# Power_Neg.net
KiCad netlist of a schematic drawn in Altium Designer
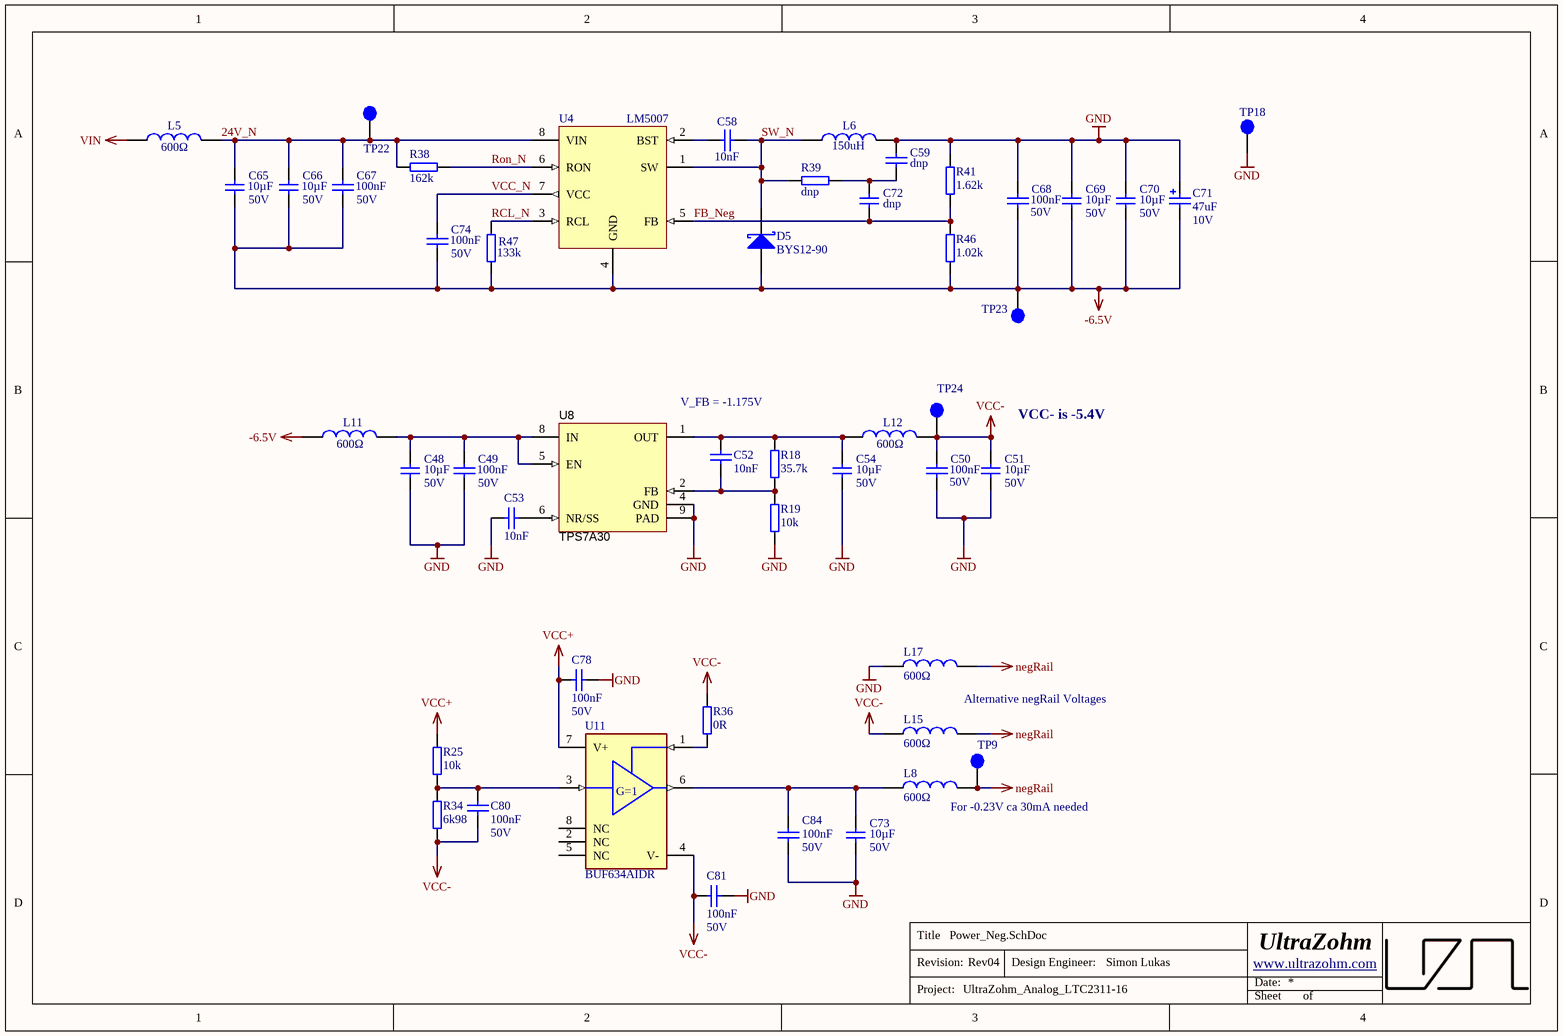
[diagram p0: Power_Neg.SchDoc]

(export (version "E")
  (design (tool "Eeschema 10.0.6"))
  (components
    (comp (ref "C48")
      (value "10µF")
      (footprint "C_1206")
      (description "Capacitor 1206")
      (fields
        (field (name "TOLERANCE") "10%")
        (field (name "MF") "Samsung")
        (field (name "VOLTAGE") "50V")
        (field (name "CREATED") "2020_09_17_Liegmann")
      )
      (libsource (lib "UltraZohm_ADC") (part "C_1206"))
    )
    (comp (ref "C49")
      (value "100nF")
      (footprint "CAPC1608X07N")
      (fields
        (field (name "MF") "Yageo")
        (field (name "MPN") "CC0603KRX7R9BB104")
        (field (name "VOLTAGE") "50V")
        (field (name "TOLERANCE") "10%")
      )
      (libsource (lib "UltraZohm_ADC") (part "Cap_0603"))
    )
    (comp (ref "C50")
      (value "100nF")
      (footprint "CAPC1608X07N")
      (fields
        (field (name "MF") "Yageo")
        (field (name "MPN") "CC0603KRX7R9BB104")
        (field (name "VOLTAGE") "50V")
        (field (name "TOLERANCE") "10%")
      )
      (libsource (lib "UltraZohm_ADC") (part "Cap_0603"))
    )
    (comp (ref "C51")
      (value "10µF")
      (footprint "C_1206")
      (description "Capacitor 1206")
      (fields
        (field (name "TOLERANCE") "10%")
        (field (name "MF") "Samsung")
        (field (name "VOLTAGE") "50V")
        (field (name "CREATED") "2020_09_17_Liegmann")
      )
      (libsource (lib "UltraZohm_ADC") (part "C_1206"))
    )
    (comp (ref "C52")
      (value "10nF")
      (footprint "CAPC1608X07N")
      (fields
        (field (name "MF") "Würth Elektronik")
        (field (name "MPN") "885012206065")
        (field (name "VOLTAGE") "25V")
      )
      (libsource (lib "UltraZohm_ADC") (part "Cap_0603"))
    )
    (comp (ref "C53")
      (value "10nF")
      (footprint "CAPC1608X07N")
      (fields
        (field (name "MF") "Würth Elektronik")
        (field (name "MPN") "885012206065")
        (field (name "VOLTAGE") "25V")
      )
      (libsource (lib "UltraZohm_ADC") (part "Cap_0603"))
    )
    (comp (ref "C54")
      (value "10µF")
      (footprint "C_1206")
      (description "Capacitor 1206")
      (fields
        (field (name "TOLERANCE") "10%")
        (field (name "MF") "Samsung")
        (field (name "VOLTAGE") "50V")
        (field (name "CREATED") "2020_09_17_Liegmann")
      )
      (libsource (lib "UltraZohm_ADC") (part "C_1206"))
    )
    (comp (ref "C58")
      (value "10nF")
      (footprint "CAPC1608X07N")
      (fields
        (field (name "MF") "Würth Elektronik")
        (field (name "MPN") "885012206065")
        (field (name "VOLTAGE") "25V")
      )
      (libsource (lib "UltraZohm_ADC") (part "Cap_0603"))
    )
    (comp (ref "C59")
      (value "dnp")
      (footprint "CAPC1608X07N")
      (fields
        (field (name "MF") "KEMET")
        (field (name "MPN") "C0603C752J3GACTU")
        (field (name "VOLTAGE") "25V")
      )
      (libsource (lib "UltraZohm_ADC") (part "Cap_0603"))
    )
    (comp (ref "C65")
      (value "10µF")
      (footprint "C_1206")
      (description "Capacitor 1206")
      (fields (field (name "TOLERANCE") "20%") (field (name "MF") "Samsung") (field (name "VOLTAGE") "50V"))
      (libsource (lib "UltraZohm_ADC") (part "C_1206"))
    )
    (comp (ref "C66")
      (value "10µF")
      (footprint "C_1206")
      (description "Capacitor 1206")
      (fields (field (name "TOLERANCE") "20%") (field (name "MF") "Samsung") (field (name "VOLTAGE") "50V"))
      (libsource (lib "UltraZohm_ADC") (part "C_1206"))
    )
    (comp (ref "C67")
      (value "100nF")
      (footprint "CAPC1608X07N")
      (fields
        (field (name "MF") "Yageo")
        (field (name "MPN") "CC0603KRX7R9BB104")
        (field (name "VOLTAGE") "50V")
        (field (name "TOLERANCE") "10%")
      )
      (libsource (lib "UltraZohm_ADC") (part "Cap_0603"))
    )
    (comp (ref "C68")
      (value "100nF")
      (footprint "CAPC1608X07N")
      (fields
        (field (name "MF") "Yageo")
        (field (name "MPN") "CC0603KRX7R9BB104")
        (field (name "VOLTAGE") "50V")
        (field (name "TOLERANCE") "10%")
      )
      (libsource (lib "UltraZohm_ADC") (part "Cap_0603"))
    )
    (comp (ref "C69")
      (value "10µF")
      (footprint "C_1206")
      (description "Capacitor 1206")
      (fields
        (field (name "TOLERANCE") "10%")
        (field (name "MF") "Samsung")
        (field (name "VOLTAGE") "50V")
        (field (name "CREATED") "2020_09_17_Liegmann")
      )
      (libsource (lib "UltraZohm_ADC") (part "C_1206"))
    )
    (comp (ref "C70")
      (value "10µF")
      (footprint "C_1206")
      (description "Capacitor 1206")
      (fields
        (field (name "TOLERANCE") "10%")
        (field (name "MF") "Samsung")
        (field (name "VOLTAGE") "50V")
        (field (name "CREATED") "2020_09_17_Liegmann")
      )
      (libsource (lib "UltraZohm_ADC") (part "C_1206"))
    )
    (comp (ref "C71")
      (value "47uF")
      (footprint "WCAP-ASLI_5x5.5")
      (description "WCAP-ASLI Aluminum Electrolytic Capacitor, V-Chip, SMT, D5xH5.5mm, 47uF, 10V")
      (fields
        (field (name "MPN") "865080242004")
        (field (name "MF") "Wurth Elektronik")
        (field (name "VOLTAGE") "10V")
      )
      (libsource (lib "UltraZohm_ADC") (part "865080142007"))
    )
    (comp (ref "C72")
      (value "dnp")
      (footprint "C_1206")
      (description "Capacitor 1206")
      (fields (field (name "TOLERANCE") "5%") (field (name "MF") "Murata Electronics"))
      (libsource (lib "UltraZohm_ADC") (part "C_1206"))
    )
    (comp (ref "C73")
      (value "10µF")
      (footprint "C_1206")
      (description "Capacitor 1206")
      (fields
        (field (name "TOLERANCE") "10%")
        (field (name "MF") "Samsung")
        (field (name "VOLTAGE") "50V")
        (field (name "CREATED") "2020_09_17_Liegmann")
      )
      (libsource (lib "UltraZohm_ADC") (part "C_1206"))
    )
    (comp (ref "C74")
      (value "100nF")
      (footprint "CAPC1608X07N")
      (fields
        (field (name "MF") "Yageo")
        (field (name "MPN") "CC0603KRX7R9BB104")
        (field (name "VOLTAGE") "50V")
        (field (name "TOLERANCE") "10%")
      )
      (libsource (lib "UltraZohm_ADC") (part "Cap_0603"))
    )
    (comp (ref "C78")
      (value "100nF")
      (footprint "CAPC1608X07N")
      (fields
        (field (name "MF") "Yageo")
        (field (name "MPN") "CC0603KRX7R9BB104")
        (field (name "VOLTAGE") "50V")
      )
      (libsource (lib "UltraZohm_ADC") (part "Cap_0603"))
    )
    (comp (ref "C80")
      (value "100nF")
      (footprint "CAPC1608X07N")
      (fields
        (field (name "MF") "Yageo")
        (field (name "MPN") "CC0603KRX7R9BB104")
        (field (name "VOLTAGE") "50V")
      )
      (libsource (lib "UltraZohm_ADC") (part "Cap_0603"))
    )
    (comp (ref "C81")
      (value "100nF")
      (footprint "CAPC1608X07N")
      (fields
        (field (name "MF") "Yageo")
        (field (name "MPN") "CC0603KRX7R9BB104")
        (field (name "VOLTAGE") "50V")
      )
      (libsource (lib "UltraZohm_ADC") (part "Cap_0603"))
    )
    (comp (ref "C84")
      (value "100nF")
      (footprint "CAPC1608X07N")
      (fields
        (field (name "MF") "Yageo")
        (field (name "MPN") "CC0603KRX7R9BB104")
        (field (name "VOLTAGE") "50V")
      )
      (libsource (lib "UltraZohm_ADC") (part "Cap_0603"))
    )
    (comp (ref "D5")
      (value "BYS12-90")
      (footprint "DIOM4227X23N")
      (description "Schottky Diode")
      (fields (field (name "MF") "Vishay") (field (name "MPN") "BYS12-90-E3/TR3"))
      (libsource (lib "UltraZohm_ADC") (part "BYS12-90"))
    )
    (comp (ref "L5")
      (value "600Ω")
      (footprint "WE-CBF_0805_High Current")
      (description "WE-CBF SMD EMI Suppression Ferrite Bead, 0805, 600Ω")
      (fields (field (name "MF") "Würth Elektronik") (field (name "MPN") "742792040"))
      (libsource (lib "UltraZohm_ADC") (part "WE-CBF, 742792040"))
    )
    (comp (ref "L6")
      (value "150uH")
      (footprint "SMT_inductor_1050_Performance")
      (description "SMT power Inductor, 150uH, 320m DRC")
      (fields (field (name "MF") "EPCOS / TDK") (field (name "MPN") "B82464G4154M"))
      (libsource (lib "UltraZohm_ADC") (part "B82464G4154M"))
    )
    (comp (ref "L8")
      (value "600Ω")
      (footprint "WE-CBF_0805_High Current")
      (description "WE-CBF SMD EMI Suppression Ferrite Bead, 0805, 600Ω")
      (fields (field (name "MF") "Wurth Elektronik") (field (name "MPN") "742792040"))
      (libsource (lib "UltraZohm_ADC") (part "WE-CBF, 742792040"))
    )
    (comp (ref "L11")
      (value "600Ω")
      (footprint "WE-CBF_0805_High Current")
      (description "WE-CBF SMD EMI Suppression Ferrite Bead, 0805, 600Ω")
      (fields (field (name "MF") "Würth Elektronik") (field (name "MPN") "742792040"))
      (libsource (lib "UltraZohm_ADC") (part "WE-CBF, 742792040"))
    )
    (comp (ref "L12")
      (value "600Ω")
      (footprint "WE-CBF_0805_High Current")
      (description "WE-CBF SMD EMI Suppression Ferrite Bead, 0805, 600Ω")
      (fields (field (name "MF") "Würth Elektronik") (field (name "MPN") "742792040"))
      (libsource (lib "UltraZohm_ADC") (part "WE-CBF, 742792040"))
    )
    (comp (ref "L15")
      (value "600Ω")
      (footprint "WE-CBF_0805_High Current")
      (description "WE-CBF SMD EMI Suppression Ferrite Bead, 0805, 600Ω")
      (fields (field (name "MF") "Wurth Elektronik") (field (name "MPN") "742792040"))
      (libsource (lib "UltraZohm_ADC") (part "WE-CBF, 742792040"))
    )
    (comp (ref "L17")
      (value "600Ω")
      (footprint "WE-CBF_0805_High Current")
      (description "WE-CBF SMD EMI Suppression Ferrite Bead, 0805, 600Ω")
      (fields (field (name "MF") "Wurth Elektronik") (field (name "MPN") "742792040"))
      (libsource (lib "UltraZohm_ADC") (part "WE-CBF, 742792040"))
    )
    (comp (ref "R18")
      (value "35.7k")
      (footprint "RESC1608X06N")
      (fields
        (field (name "MF") "Bourns")
        (field (name "MPN") "CR0603-FX-3572ELF")
        (field (name "TOLERANCE") "1%")
      )
      (libsource (lib "UltraZohm_ADC") (part "R_0603"))
    )
    (comp (ref "R19")
      (value "10k")
      (footprint "RESC1608X06N")
      (fields
        (field (name "MF") "Bourns")
        (field (name "MPN") "CR0603-FX-1002ELF")
        (field (name "TOLERANCE") "1%")
      )
      (libsource (lib "UltraZohm_ADC") (part "R_0603"))
    )
    (comp (ref "R25")
      (value "10k")
      (footprint "RESC1608X06N")
      (fields
        (field (name "MF") "Bourns")
        (field (name "MPN") "CR0603-FX-1002ELF")
        (field (name "TOLERANCE") "1%")
      )
      (libsource (lib "UltraZohm_ADC") (part "R_0603"))
    )
    (comp (ref "R34")
      (value "6k98")
      (footprint "RESC1608X06N")
      (fields
        (field (name "MF") "Bourns")
        (field (name "MPN") "CR0603-FX-6981ELF")
        (field (name "TOLERANCE") "1%")
      )
      (libsource (lib "UltraZohm_ADC") (part "R_0603"))
    )
    (comp (ref "R36")
      (value "0R")
      (footprint "RESC1608X06N")
      (fields (field (name "MF") "Vishay / Dale") (field (name "MPN") "CRCW06030000Z0EBC"))
      (libsource (lib "UltraZohm_ADC") (part "R_0603"))
    )
    (comp (ref "R38")
      (value "162k")
      (footprint "RESC1608X06N")
      (fields (field (name "MF") "Bourns") (field (name "MPN") "CR0603-FX-1623ELF"))
      (libsource (lib "UltraZohm_ADC") (part "R_0603"))
    )
    (comp (ref "R39")
      (value "dnp")
      (footprint "RESC1608X06N")
      (fields (field (name "MF") "Yageo") (field (name "MPN") "AC0603FR-1375KL"))
      (libsource (lib "UltraZohm_ADC") (part "R_0603"))
    )
    (comp (ref "R41")
      (value "1.62k")
      (footprint "RESC1608X06N")
      (fields
        (field (name "MF") "Bourns")
        (field (name "MPN") "CR0603-FX-1621ELF")
        (field (name "TOLERANCE") "1%")
      )
      (libsource (lib "UltraZohm_ADC") (part "R_0603"))
    )
    (comp (ref "R46")
      (value "1.02k")
      (footprint "RESC1608X06N")
      (fields
        (field (name "MF") "Bourns")
        (field (name "MPN") "CR0603-FX-1021ELF")
        (field (name "TOLERANCE") "1%")
      )
      (libsource (lib "UltraZohm_ADC") (part "R_0603"))
    )
    (comp (ref "R47")
      (value "133k")
      (footprint "RESC1608X06N")
      (fields (field (name "MF") "Bourns") (field (name "MPN") "CR0603-FX-1333ELF"))
      (libsource (lib "UltraZohm_ADC") (part "R_0603"))
    )
    (comp (ref "TP9")
      (value "negRail")
      (footprint "TP_1mm")
      (description "Testpoint 1mm")
      (fields (field (name "CREATED") "2018_06_25_AGeiger"))
      (libsource (lib "UltraZohm_ADC") (part "TP_1mm"))
    )
    (comp (ref "TP18")
      (value "GND")
      (footprint "TP_1mm")
      (description "Testpoint 1mm")
      (fields (field (name "CREATED") "2018_06_25_AGeiger"))
      (libsource (lib "UltraZohm_ADC") (part "TP_1mm"))
    )
    (comp (ref "TP22")
      (value "VIN")
      (footprint "TP_1mm")
      (description "Testpoint 1mm")
      (fields (field (name "CREATED") "2018_06_25_AGeiger"))
      (libsource (lib "UltraZohm_ADC") (part "TP_1mm"))
    )
    (comp (ref "TP23")
      (value "-6.5V")
      (footprint "TP_1mm")
      (description "Testpoint 1mm")
      (fields (field (name "CREATED") "2018_06_25_AGeiger"))
      (libsource (lib "UltraZohm_ADC") (part "TP_1mm"))
    )
    (comp (ref "TP24")
      (value "VCC-")
      (footprint "TP_1mm")
      (description "Testpoint 1mm")
      (fields (field (name "CREATED") "2018_06_25_AGeiger"))
      (libsource (lib "UltraZohm_ADC") (part "TP_1mm"))
    )
    (comp (ref "U4")
      (value "LM5007")
      (footprint "TSOP65P490X110-8N")
      (description "Buck Converter, 9-75Vin, 2.5-73Vout")
      (fields (field (name "MF") "Texas Instruments") (field (name "MPN") "LM5007MM/NOPB"))
      (libsource (lib "UltraZohm_ADC") (part "LM5007"))
    )
    (comp (ref "U8")
      (value "TPS7A30")
      (footprint "DGN0008D_N")
      (fields (field (name "MF") "Texas Instruments") (field (name "MPN") "TPS7A3001DGN"))
      (libsource (lib "UltraZohm_ADC") (part "TPS7A3001DGN"))
    )
    (comp (ref "U11")
      (value "BUF634AIDR")
      (footprint "FP-BUF634AIDR-MFG")
      (description "IC OP AMP BUFFER 8SOIC")
      (fields
        (field (name "MF") "Texas Instruments")
        (field (name "OCTOPART") "https://octopart.com/buf634aidr-texas+instruments-99505311")
      )
      (libsource (lib "UltraZohm_ADC") (part "BUF634A"))
    )
  )
  (nets
    (net (code "1") (name "-6.5V") (class "Default")
      (node (ref "C65") (pin "1") (pinfunction "1_1") (pintype "passive"))
      (node (ref "C66") (pin "1") (pinfunction "1_1") (pintype "passive"))
      (node (ref "C67") (pin "2") (pinfunction "2_2") (pintype "passive"))
      (node (ref "C68") (pin "1") (pinfunction "1_1") (pintype "passive"))
      (node (ref "C69") (pin "1") (pinfunction "1_1") (pintype "passive"))
      (node (ref "C70") (pin "1") (pinfunction "1_1") (pintype "passive"))
      (node (ref "C71") (pin "1") (pinfunction "N_1") (pintype "passive"))
      (node (ref "C74") (pin "2") (pinfunction "2_2") (pintype "passive"))
      (node (ref "D5") (pin "2") (pinfunction "A_2") (pintype "passive"))
      (node (ref "L11") (pin "1") (pinfunction "1_1") (pintype "passive"))
      (node (ref "R46") (pin "2") (pintype "passive"))
      (node (ref "R47") (pin "1") (pintype "passive"))
      (node (ref "TP23") (pin "1") (pintype "passive"))
      (node (ref "U4") (pin "4") (pinfunction "GND_4") (pintype "power_in"))
    )
    (net (code "2") (name "/24V_N") (class "Default")
      (node (ref "C65") (pin "2") (pinfunction "2_2") (pintype "passive"))
      (node (ref "C66") (pin "2") (pinfunction "2_2") (pintype "passive"))
      (node (ref "C67") (pin "1") (pinfunction "1_1") (pintype "passive"))
      (node (ref "L5") (pin "2") (pinfunction "2_2") (pintype "passive"))
      (node (ref "R38") (pin "2") (pintype "passive"))
      (node (ref "TP22") (pin "1") (pintype "passive"))
      (node (ref "U4") (pin "8") (pinfunction "VIN_8") (pintype "power_in"))
    )
    (net (code "3") (name "/FB_Neg") (class "Default")
      (node (ref "C72") (pin "2") (pinfunction "2_2") (pintype "passive"))
      (node (ref "R41") (pin "2") (pintype "passive"))
      (node (ref "R46") (pin "1") (pintype "passive"))
      (node (ref "U4") (pin "5") (pinfunction "FB_5") (pintype "input"))
    )
    (net (code "4") (name "/RCL_N") (class "Default")
      (node (ref "R47") (pin "2") (pintype "passive"))
      (node (ref "U4") (pin "3") (pinfunction "RCL_3") (pintype "input"))
    )
    (net (code "5") (name "/Ron_N") (class "Default")
      (node (ref "R38") (pin "1") (pintype "passive"))
      (node (ref "U4") (pin "6") (pinfunction "RON_6") (pintype "input"))
    )
    (net (code "6") (name "/SW_N") (class "Default")
      (node (ref "C58") (pin "1") (pinfunction "1_1") (pintype "passive"))
      (node (ref "D5") (pin "1") (pinfunction "K_1") (pintype "passive"))
      (node (ref "L6") (pin "1") (pinfunction "1_1") (pintype "passive"))
      (node (ref "R39") (pin "2") (pintype "passive"))
      (node (ref "U4") (pin "1") (pinfunction "SW_1") (pintype "power_in"))
    )
    (net (code "7") (name "/VCC_N") (class "Default")
      (node (ref "C74") (pin "1") (pinfunction "1_1") (pintype "passive"))
      (node (ref "U4") (pin "7") (pinfunction "VCC_7") (pintype "output"))
    )
    (net (code "8") (name "GND") (class "Default")
      (node (ref "C48") (pin "1") (pinfunction "1_1") (pintype "passive"))
      (node (ref "C49") (pin "2") (pinfunction "2_2") (pintype "passive"))
      (node (ref "C50") (pin "1") (pinfunction "1_1") (pintype "passive"))
      (node (ref "C51") (pin "1") (pinfunction "1_1") (pintype "passive"))
      (node (ref "C53") (pin "2") (pinfunction "2_2") (pintype "passive"))
      (node (ref "C54") (pin "1") (pinfunction "1_1") (pintype "passive"))
      (node (ref "C59") (pin "1") (pinfunction "1_1") (pintype "passive"))
      (node (ref "C68") (pin "2") (pinfunction "2_2") (pintype "passive"))
      (node (ref "C69") (pin "2") (pinfunction "2_2") (pintype "passive"))
      (node (ref "C70") (pin "2") (pinfunction "2_2") (pintype "passive"))
      (node (ref "C71") (pin "2") (pinfunction "P_2") (pintype "passive"))
      (node (ref "C73") (pin "1") (pinfunction "1_1") (pintype "passive"))
      (node (ref "C78") (pin "1") (pinfunction "1_1") (pintype "passive"))
      (node (ref "C81") (pin "1") (pinfunction "1_1") (pintype "passive"))
      (node (ref "C84") (pin "1") (pinfunction "1_1") (pintype "passive"))
      (node (ref "L17") (pin "1") (pinfunction "1_1") (pintype "passive"))
      (node (ref "L6") (pin "2") (pinfunction "2_2") (pintype "passive"))
      (node (ref "R19") (pin "2") (pintype "passive"))
      (node (ref "R41") (pin "1") (pintype "passive"))
      (node (ref "TP18") (pin "1") (pintype "passive"))
      (node (ref "U8") (pin "4") (pinfunction "GND_4") (pintype "power_in"))
      (node (ref "U8") (pin "9") (pinfunction "PAD_9") (pintype "passive"))
    )
    (net (code "9") (name "Net-(C59-Pad2)") (class "Default")
      (node (ref "C59") (pin "2") (pinfunction "2_2") (pintype "passive"))
      (node (ref "C72") (pin "1") (pinfunction "1_1") (pintype "passive"))
      (node (ref "R39") (pin "1") (pintype "passive"))
    )
    (net (code "10") (name "Net-(U4-BST)") (class "Default")
      (node (ref "C58") (pin "2") (pinfunction "2_2") (pintype "passive"))
      (node (ref "U4") (pin "2") (pinfunction "BST_2") (pintype "input"))
    )
    (net (code "11") (name "Net-(U8-EN)") (class "Default")
      (node (ref "C48") (pin "2") (pinfunction "2_2") (pintype "passive"))
      (node (ref "C49") (pin "1") (pinfunction "1_1") (pintype "passive"))
      (node (ref "L11") (pin "2") (pinfunction "2_2") (pintype "passive"))
      (node (ref "U8") (pin "5") (pinfunction "EN_5") (pintype "input"))
      (node (ref "U8") (pin "8") (pinfunction "IN_8") (pintype "power_in"))
    )
    (net (code "12") (name "Net-(U8-FB)") (class "Default")
      (node (ref "C52") (pin "2") (pinfunction "2_2") (pintype "passive"))
      (node (ref "R18") (pin "2") (pintype "passive"))
      (node (ref "R19") (pin "1") (pintype "passive"))
      (node (ref "U8") (pin "2") (pinfunction "FB_2") (pintype "input"))
    )
    (net (code "13") (name "Net-(U8-NR{slash}SS)") (class "Default")
      (node (ref "C53") (pin "1") (pinfunction "1_1") (pintype "passive"))
      (node (ref "U8") (pin "6") (pinfunction "NR/SS_6") (pintype "input"))
    )
    (net (code "14") (name "Net-(U8-OUT)") (class "Default")
      (node (ref "C52") (pin "1") (pinfunction "1_1") (pintype "passive"))
      (node (ref "C54") (pin "2") (pinfunction "2_2") (pintype "passive"))
      (node (ref "L12") (pin "1") (pinfunction "1_1") (pintype "passive"))
      (node (ref "R18") (pin "1") (pintype "passive"))
      (node (ref "U8") (pin "1") (pinfunction "OUT_1") (pintype "power_in"))
    )
    (net (code "15") (name "Net-(U11-BW)") (class "Default")
      (node (ref "R36") (pin "1") (pintype "passive"))
      (node (ref "U11") (pin "1") (pinfunction "BW_1") (pintype "input"))
    )
    (net (code "16") (name "Net-(U11-VIN)") (class "Default")
      (node (ref "C80") (pin "1") (pinfunction "1_1") (pintype "passive"))
      (node (ref "R25") (pin "1") (pintype "passive"))
      (node (ref "R34") (pin "2") (pintype "passive"))
      (node (ref "U11") (pin "3") (pinfunction "VIN_3") (pintype "input"))
    )
    (net (code "17") (name "Net-(U11-VO)") (class "Default")
      (node (ref "C73") (pin "2") (pinfunction "2_2") (pintype "passive"))
      (node (ref "C84") (pin "2") (pinfunction "2_2") (pintype "passive"))
      (node (ref "L8") (pin "1") (pinfunction "1_1") (pintype "passive"))
      (node (ref "U11") (pin "6") (pinfunction "VO_6") (pintype "output"))
    )
    (net (code "18") (name "VCC+") (class "Default")
      (node (ref "C78") (pin "2") (pinfunction "2_2") (pintype "passive"))
      (node (ref "R25") (pin "2") (pintype "passive"))
      (node (ref "U11") (pin "7") (pinfunction "V+_7") (pintype "power_in"))
    )
    (net (code "19") (name "VCC-") (class "Default")
      (node (ref "C50") (pin "2") (pinfunction "2_2") (pintype "passive"))
      (node (ref "C51") (pin "2") (pinfunction "2_2") (pintype "passive"))
      (node (ref "C80") (pin "2") (pinfunction "2_2") (pintype "passive"))
      (node (ref "C81") (pin "2") (pinfunction "2_2") (pintype "passive"))
      (node (ref "L12") (pin "2") (pinfunction "2_2") (pintype "passive"))
      (node (ref "L15") (pin "1") (pinfunction "1_1") (pintype "passive"))
      (node (ref "R34") (pin "1") (pintype "passive"))
      (node (ref "R36") (pin "2") (pintype "passive"))
      (node (ref "TP24") (pin "1") (pintype "passive"))
      (node (ref "U11") (pin "4") (pinfunction "V-_4") (pintype "power_in"))
    )
    (net (code "20") (name "VIN") (class "Default")
      (node (ref "L5") (pin "1") (pinfunction "1_1") (pintype "passive"))
    )
    (net (code "21") (name "negRail") (class "Default")
      (node (ref "L15") (pin "2") (pinfunction "2_2") (pintype "passive"))
      (node (ref "L17") (pin "2") (pinfunction "2_2") (pintype "passive"))
      (node (ref "L8") (pin "2") (pinfunction "2_2") (pintype "passive"))
      (node (ref "TP9") (pin "1") (pintype "passive"))
    )
    (net (code "22") (name "unconnected-(U8-DNC-Pad7)") (class "Default")
      (node (ref "U8") (pin "7") (pinfunction "DNC_7") (pintype "passive"))
    )
    (net (code "23") (name "unconnected-(U8-NC-Pad3)") (class "Default")
      (node (ref "U8") (pin "3") (pinfunction "NC_3") (pintype "passive"))
    )
    (net (code "24") (name "unconnected-(U11-NC-Pad2)") (class "Default")
      (node (ref "U11") (pin "2") (pinfunction "NC_2") (pintype "passive"))
    )
    (net (code "25") (name "unconnected-(U11-NC-Pad5)") (class "Default")
      (node (ref "U11") (pin "5") (pinfunction "NC_5") (pintype "passive"))
    )
    (net (code "26") (name "unconnected-(U11-NC-Pad8)") (class "Default")
      (node (ref "U11") (pin "8") (pinfunction "NC_8") (pintype "passive"))
    )
  )
)
